# PWR_RT5715.net
KiCad netlist of a schematic drawn in Altium Designer
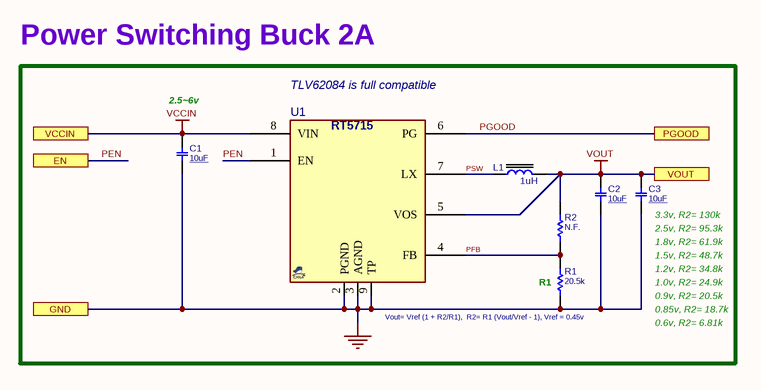
[diagram p0: PWR_RT5715.SchDoc]

(export (version "E")
  (design (tool "Eeschema 10.0.6"))
  (components
    (comp (ref "C1")
      (value "10uF")
      (footprint "C0402")
      (description "CAP, MLCC")
      (libsource (lib "passive_smd") (part "CAP_SMD_MLCC"))
    )
    (comp (ref "C2")
      (value "10uF")
      (footprint "C0402")
      (description "CAP, MLCC")
      (libsource (lib "passive_smd") (part "CAP_SMD_MLCC"))
    )
    (comp (ref "C3")
      (value "10uF")
      (footprint "C0402")
      (description "CAP, MLCC")
      (libsource (lib "passive_smd") (part "CAP_SMD_MLCC"))
    )
    (comp (ref "L1")
      (value "1uH")
      (footprint "L0806")
      (description "INDUCTOR, POWER, SMD")
      (fields (field (name "MANF") "Murata") (field (name "MANF_P#") "DFE201610E-1R0M"))
      (libsource (lib "passive_smd") (part "INDPWR_SMD"))
    )
    (comp (ref "R1")
      (value "20.5k")
      (footprint "R0402A")
      (description "RESISTOR, SMD")
      (libsource (lib "passive_smd") (part "RES_SMD"))
    )
    (comp (ref "R2")
      (value "N.F.")
      (footprint "R0402A")
      (description "RESISTOR, SMD")
      (libsource (lib "passive_smd") (part "RES_SMD"))
    )
    (comp (ref "U1")
      (value "RT5715")
      (footprint "SON50_8T_2020")
      (description "REG, Switching, Buck, 2A, ADJ, 2.7MHz, 2.5~5.5VIN, SON-8")
      (fields (field (name "MANF_P#") "RT5715GQW") (field (name "MANF") "Richtek"))
      (libsource (lib "pwr_switching_buck") (part "VREG_RT5715_SON8"))
    )
  )
  (nets
    (net (code "1") (name "/PEN") (class "Default")
      (node (ref "U1") (pin "1") (pinfunction "EN_1") (pintype "passive"))
    )
    (net (code "2") (name "/PFB") (class "Default")
      (node (ref "R1") (pin "2") (pinfunction "2_2") (pintype "passive"))
      (node (ref "R2") (pin "1") (pinfunction "1_1") (pintype "passive"))
      (node (ref "U1") (pin "4") (pinfunction "FB_4") (pintype "passive"))
    )
    (net (code "3") (name "/PGOOD") (class "Default")
      (node (ref "U1") (pin "6") (pinfunction "PG_6") (pintype "passive"))
    )
    (net (code "4") (name "/PSW") (class "Default")
      (node (ref "L1") (pin "1") (pinfunction "1_1") (pintype "passive"))
      (node (ref "U1") (pin "7") (pinfunction "LX_7") (pintype "passive"))
    )
    (net (code "5") (name "GND") (class "Default")
      (node (ref "C1") (pin "2") (pinfunction "2_2") (pintype "passive"))
      (node (ref "C2") (pin "2") (pinfunction "2_2") (pintype "passive"))
      (node (ref "C3") (pin "2") (pinfunction "2_2") (pintype "passive"))
      (node (ref "R1") (pin "1") (pinfunction "1_1") (pintype "passive"))
      (node (ref "U1") (pin "2") (pinfunction "PGND_2") (pintype "passive"))
      (node (ref "U1") (pin "3") (pinfunction "AGND_3") (pintype "passive"))
      (node (ref "U1") (pin "9") (pinfunction "TP_9") (pintype "passive"))
    )
    (net (code "6") (name "VCCIN") (class "Default")
      (node (ref "C1") (pin "1") (pinfunction "1_1") (pintype "passive"))
      (node (ref "U1") (pin "8") (pinfunction "VIN_8") (pintype "passive"))
    )
    (net (code "7") (name "VOUT") (class "Default")
      (node (ref "C2") (pin "1") (pinfunction "1_1") (pintype "passive"))
      (node (ref "C3") (pin "1") (pinfunction "1_1") (pintype "passive"))
      (node (ref "L1") (pin "2") (pinfunction "2_2") (pintype "passive"))
      (node (ref "R2") (pin "2") (pinfunction "2_2") (pintype "passive"))
      (node (ref "U1") (pin "5") (pinfunction "VOS_5") (pintype "passive"))
    )
  )
)
